# GPS_Altimetro_BoosterPack.net
KiCad netlist of a schematic drawn in Altium Designer
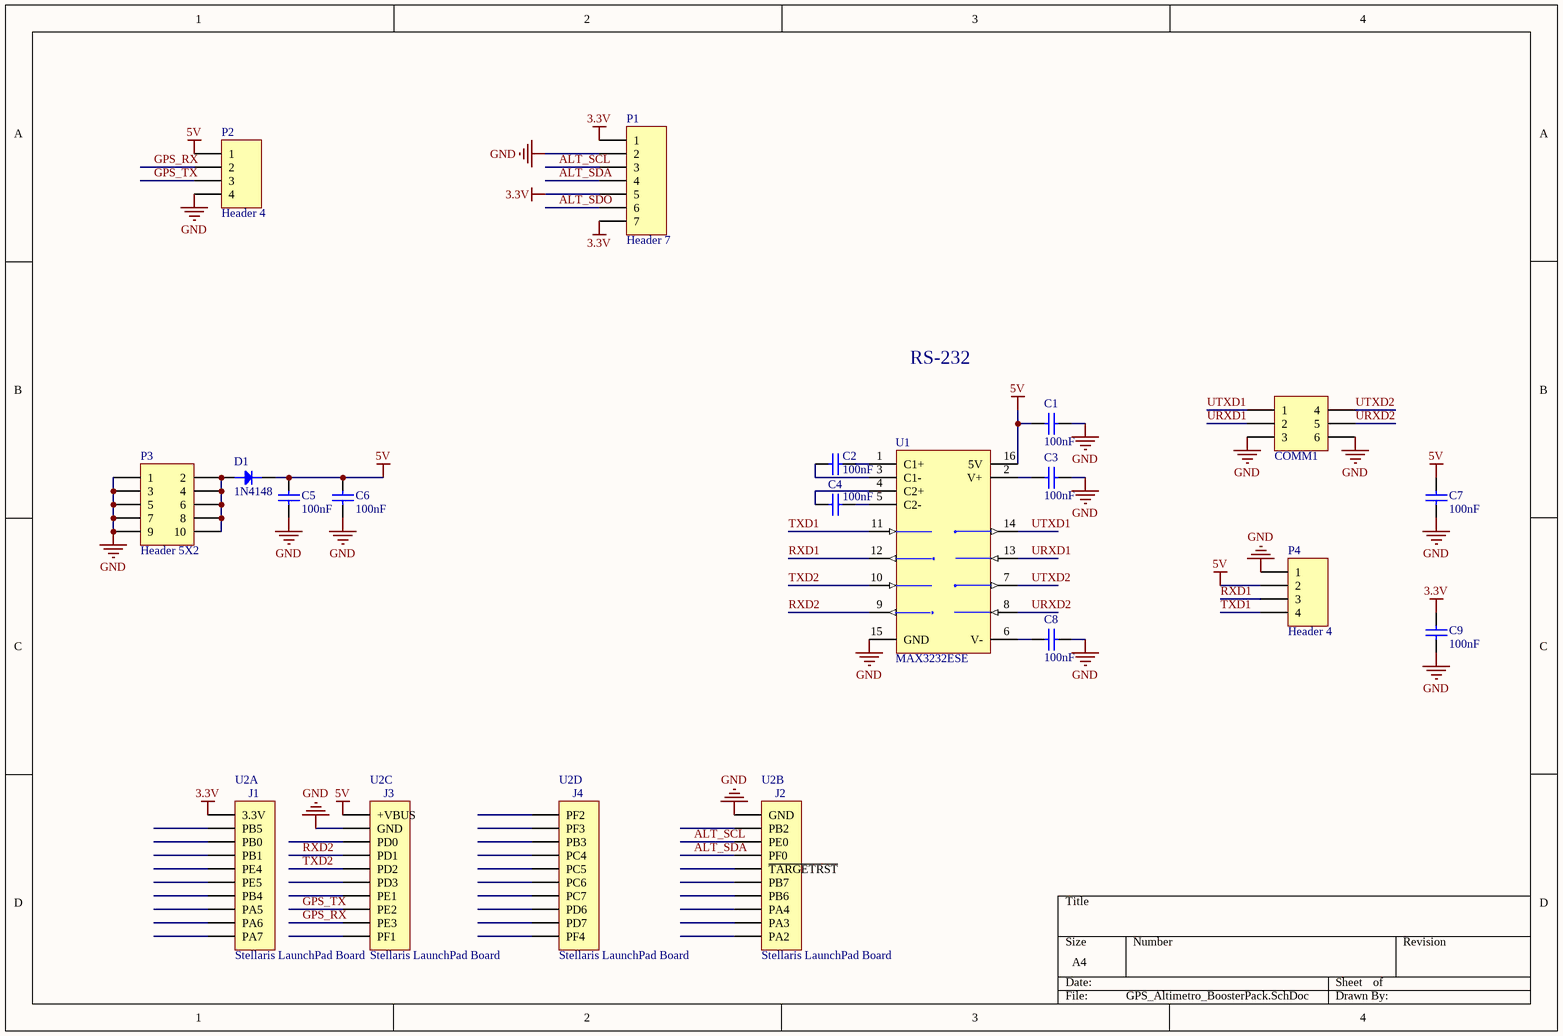
[diagram p0: GPS_Altimetro_BoosterPack.SchDoc]

(export (version "E")
  (design (tool "Eeschema 10.0.6"))
  (components
    (comp (ref "C1")
      (value "100nF")
      (footprint "0805_CAP")
      (fields (field (name "Comment") "Capacitor"))
      (libsource (lib "epf") (part "Cap"))
    )
    (comp (ref "C2")
      (value "100nF")
      (footprint "0805_CAP")
      (fields (field (name "Comment") "Capacitor"))
      (libsource (lib "epf") (part "Cap"))
    )
    (comp (ref "C3")
      (value "100nF")
      (footprint "0805_CAP")
      (fields (field (name "Comment") "Capacitor"))
      (libsource (lib "epf") (part "Cap"))
    )
    (comp (ref "C4")
      (value "100nF")
      (footprint "0805_CAP")
      (fields (field (name "Comment") "Capacitor"))
      (libsource (lib "epf") (part "Cap"))
    )
    (comp (ref "C5")
      (value "100nF")
      (footprint "0805_CAP")
      (fields (field (name "Comment") "Capacitor"))
      (libsource (lib "epf") (part "Cap"))
    )
    (comp (ref "C6")
      (value "100nF")
      (footprint "0805_CAP")
      (fields (field (name "Comment") "Capacitor"))
      (libsource (lib "epf") (part "Cap"))
    )
    (comp (ref "C7")
      (value "100nF")
      (footprint "0805_CAP")
      (fields (field (name "Comment") "Capacitor"))
      (libsource (lib "epf") (part "Cap"))
    )
    (comp (ref "C8")
      (value "100nF")
      (footprint "0805_CAP")
      (fields (field (name "Comment") "Capacitor"))
      (libsource (lib "epf") (part "Cap"))
    )
    (comp (ref "C9")
      (value "100nF")
      (footprint "0805_CAP")
      (fields (field (name "Comment") "Capacitor"))
      (libsource (lib "epf") (part "Cap"))
    )
    (comp (ref "COMM1")
      (value "AP_COMM")
      (footprint "HDR2X3_CEN")
      (description "Header, 3-Pin, Dual row")
      (fields (field (name "PUBLISHER") "Altium Limited"))
      (libsource (lib "epf") (part "AP_COMM"))
    )
    (comp (ref "D1") (value "1N4148") (footprint "1N4148SMD") (libsource (lib "epf") (part "1N4148")))
    (comp (ref "P1")
      (value "Header 7")
      (footprint "HDR1X7")
      (description "Header, 7-Pin")
      (fields (field (name "PUBLISHER") "Altium Limited"))
      (libsource (lib "Miscellaneous Connectors") (part "Header 7"))
    )
    (comp (ref "P2")
      (value "Header 4")
      (footprint "HDR1X4")
      (description "Header, 4-Pin")
      (fields (field (name "PUBLISHER") "Altium Limited"))
      (libsource (lib "Miscellaneous Connectors") (part "Header 4"))
    )
    (comp (ref "P3")
      (value "Header 5X2")
      (footprint "HDR2X5")
      (description "Header, 5-Pin, Dual row")
      (fields (field (name "PUBLISHER") "Altium Limited"))
      (libsource (lib "Miscellaneous Connectors") (part "Header 5X2"))
    )
    (comp (ref "P4")
      (value "Header 4")
      (footprint "HDR1X4")
      (description "Header, 4-Pin")
      (fields (field (name "PUBLISHER") "Altium Limited"))
      (libsource (lib "Miscellaneous Connectors") (part "Header 4"))
    )
    (comp (ref "U1")
      (value "MAX3232ESE")
      (footprint "SOIC127P602-16BN")
      (libsource (lib "epf") (part "MAX3232ESE+"))
    )
    (comp (ref "U2")
      (value "Stellaris LaunchPad Board")
      (footprint "LaunchPad")
      (description "Stellaris LaunchPad board")
      (fields (field (name "PUBLISHER") "Altium Limited"))
      (libsource (lib "epf") (part "Stellaris LaunchPad Board"))
    )
  )
  (nets
    (net (code "1") (name "/ALT_SCL") (class "Default")
      (node (ref "P1") (pin "3") (pinfunction "3_3") (pintype "passive"))
      (node (ref "U2") (pin "13") (pinfunction "PE0_13") (pintype "passive"))
    )
    (net (code "2") (name "/ALT_SDA") (class "Default")
      (node (ref "P1") (pin "4") (pinfunction "4_4") (pintype "passive"))
      (node (ref "U2") (pin "14") (pinfunction "PF0_14") (pintype "passive"))
    )
    (net (code "3") (name "/ALT_SDO") (class "Default")
      (node (ref "P1") (pin "6") (pinfunction "6_6") (pintype "passive"))
    )
    (net (code "4") (name "/GPS_RX") (class "Default")
      (node (ref "P2") (pin "2") (pinfunction "2_2") (pintype "passive"))
      (node (ref "U2") (pin "29") (pinfunction "PE3_29") (pintype "passive"))
    )
    (net (code "5") (name "/GPS_TX") (class "Default")
      (node (ref "P2") (pin "3") (pinfunction "3_3") (pintype "passive"))
      (node (ref "U2") (pin "28") (pinfunction "PE2_28") (pintype "passive"))
    )
    (net (code "6") (name "/RXD1") (class "Default")
      (node (ref "P4") (pin "3") (pinfunction "3_3") (pintype "passive"))
      (node (ref "U1") (pin "12") (pinfunction "R1OUT_12") (pintype "output"))
    )
    (net (code "7") (name "/RXD2") (class "Default")
      (node (ref "U1") (pin "9") (pinfunction "R2OUT_9") (pintype "output"))
      (node (ref "U2") (pin "24") (pinfunction "PD1_24") (pintype "passive"))
    )
    (net (code "8") (name "/TXD1") (class "Default")
      (node (ref "P4") (pin "4") (pinfunction "4_4") (pintype "passive"))
      (node (ref "U1") (pin "11") (pinfunction "T1IN_11") (pintype "input"))
    )
    (net (code "9") (name "/TXD2") (class "Default")
      (node (ref "U1") (pin "10") (pinfunction "T2IN_10") (pintype "input"))
      (node (ref "U2") (pin "25") (pinfunction "PD2_25") (pintype "passive"))
    )
    (net (code "10") (name "/URXD1") (class "Default")
      (node (ref "COMM1") (pin "2") (pinfunction "2_2") (pintype "passive"))
      (node (ref "U1") (pin "13") (pinfunction "R1IN_13") (pintype "input"))
    )
    (net (code "11") (name "/URXD2") (class "Default")
      (node (ref "COMM1") (pin "5") (pinfunction "5_5") (pintype "passive"))
      (node (ref "U1") (pin "8") (pinfunction "R2IN_8") (pintype "input"))
    )
    (net (code "12") (name "/UTXD1") (class "Default")
      (node (ref "COMM1") (pin "1") (pinfunction "1_1") (pintype "passive"))
      (node (ref "U1") (pin "14") (pinfunction "T1OUT_14") (pintype "output"))
    )
    (net (code "13") (name "/UTXD2") (class "Default")
      (node (ref "COMM1") (pin "4") (pinfunction "4_4") (pintype "passive"))
      (node (ref "U1") (pin "7") (pinfunction "T2OUT_7") (pintype "output"))
    )
    (net (code "14") (name "3.3V") (class "Default")
      (node (ref "C9") (pin "1") (pinfunction "1_1") (pintype "passive"))
      (node (ref "P1") (pin "1") (pinfunction "1_1") (pintype "passive"))
      (node (ref "P1") (pin "5") (pinfunction "5_5") (pintype "passive"))
      (node (ref "P1") (pin "7") (pinfunction "7_7") (pintype "passive"))
      (node (ref "U2") (pin "1") (pinfunction "3.3V_1") (pintype "passive"))
    )
    (net (code "15") (name "5V") (class "Default")
      (node (ref "C1") (pin "2") (pinfunction "2_2") (pintype "passive"))
      (node (ref "C5") (pin "1") (pinfunction "1_1") (pintype "passive"))
      (node (ref "C6") (pin "1") (pinfunction "1_1") (pintype "passive"))
      (node (ref "C7") (pin "1") (pinfunction "1_1") (pintype "passive"))
      (node (ref "D1") (pin "2") (pinfunction "K_2") (pintype "passive"))
      (node (ref "P2") (pin "1") (pinfunction "1_1") (pintype "passive"))
      (node (ref "P4") (pin "2") (pinfunction "2_2") (pintype "passive"))
      (node (ref "U1") (pin "16") (pinfunction "5V_16") (pintype "power_in"))
      (node (ref "U2") (pin "21") (pinfunction "+VBUS_21") (pintype "passive"))
    )
    (net (code "16") (name "GND") (class "Default")
      (node (ref "C1") (pin "1") (pinfunction "1_1") (pintype "passive"))
      (node (ref "C3") (pin "1") (pinfunction "1_1") (pintype "passive"))
      (node (ref "C5") (pin "2") (pinfunction "2_2") (pintype "passive"))
      (node (ref "C6") (pin "2") (pinfunction "2_2") (pintype "passive"))
      (node (ref "C7") (pin "2") (pinfunction "2_2") (pintype "passive"))
      (node (ref "C8") (pin "1") (pinfunction "1_1") (pintype "passive"))
      (node (ref "C9") (pin "2") (pinfunction "2_2") (pintype "passive"))
      (node (ref "COMM1") (pin "3") (pinfunction "3_3") (pintype "passive"))
      (node (ref "COMM1") (pin "6") (pinfunction "6_6") (pintype "passive"))
      (node (ref "P1") (pin "2") (pinfunction "2_2") (pintype "passive"))
      (node (ref "P2") (pin "4") (pinfunction "4_4") (pintype "passive"))
      (node (ref "P3") (pin "1") (pinfunction "1_1") (pintype "passive"))
      (node (ref "P3") (pin "3") (pinfunction "3_3") (pintype "passive"))
      (node (ref "P3") (pin "5") (pinfunction "5_5") (pintype "passive"))
      (node (ref "P3") (pin "7") (pinfunction "7_7") (pintype "passive"))
      (node (ref "P3") (pin "9") (pinfunction "9_9") (pintype "passive"))
      (node (ref "P4") (pin "1") (pinfunction "1_1") (pintype "passive"))
      (node (ref "U1") (pin "15") (pinfunction "GND_15") (pintype "power_in"))
      (node (ref "U2") (pin "11") (pinfunction "GND_11") (pintype "passive"))
      (node (ref "U2") (pin "22") (pinfunction "GND_22") (pintype "passive"))
    )
    (net (code "17") (name "Net-(D1-A)") (class "Default")
      (node (ref "D1") (pin "1") (pinfunction "A_1") (pintype "passive"))
      (node (ref "P3") (pin "10") (pinfunction "10_10") (pintype "passive"))
      (node (ref "P3") (pin "2") (pinfunction "2_2") (pintype "passive"))
      (node (ref "P3") (pin "4") (pinfunction "4_4") (pintype "passive"))
      (node (ref "P3") (pin "6") (pinfunction "6_6") (pintype "passive"))
      (node (ref "P3") (pin "8") (pinfunction "8_8") (pintype "passive"))
    )
    (net (code "18") (name "Net-(U1-C1+)") (class "Default")
      (node (ref "C2") (pin "1") (pinfunction "1_1") (pintype "passive"))
      (node (ref "U1") (pin "1") (pinfunction "C1+_1") (pintype "passive"))
    )
    (net (code "19") (name "Net-(U1-C1-)") (class "Default")
      (node (ref "C2") (pin "2") (pinfunction "2_2") (pintype "passive"))
      (node (ref "U1") (pin "3") (pinfunction "C1-_3") (pintype "passive"))
    )
    (net (code "20") (name "Net-(U1-C2+)") (class "Default")
      (node (ref "C4") (pin "2") (pinfunction "2_2") (pintype "passive"))
      (node (ref "U1") (pin "4") (pinfunction "C2+_4") (pintype "passive"))
    )
    (net (code "21") (name "Net-(U1-C2-)") (class "Default")
      (node (ref "C4") (pin "1") (pinfunction "1_1") (pintype "passive"))
      (node (ref "U1") (pin "5") (pinfunction "C2-_5") (pintype "passive"))
    )
    (net (code "22") (name "Net-(U1-V+)") (class "Default")
      (node (ref "C3") (pin "2") (pinfunction "2_2") (pintype "passive"))
      (node (ref "U1") (pin "2") (pinfunction "V+_2") (pintype "power_in"))
    )
    (net (code "23") (name "Net-(U1-V-)") (class "Default")
      (node (ref "C8") (pin "2") (pinfunction "2_2") (pintype "passive"))
      (node (ref "U1") (pin "6") (pinfunction "V-_6") (pintype "power_in"))
    )
    (net (code "24") (name "unconnected-(U2A-PA5-Pad8)") (class "Default")
      (node (ref "U2") (pin "8") (pinfunction "PA5_8") (pintype "passive"))
    )
    (net (code "25") (name "unconnected-(U2A-PA6-Pad9)") (class "Default")
      (node (ref "U2") (pin "9") (pinfunction "PA6_9") (pintype "passive"))
    )
    (net (code "26") (name "unconnected-(U2A-PA7-Pad10)") (class "Default")
      (node (ref "U2") (pin "10") (pinfunction "PA7_10") (pintype "passive"))
    )
    (net (code "27") (name "unconnected-(U2A-PB0-Pad3)") (class "Default")
      (node (ref "U2") (pin "3") (pinfunction "PB0_3") (pintype "passive"))
    )
    (net (code "28") (name "unconnected-(U2A-PB1-Pad4)") (class "Default")
      (node (ref "U2") (pin "4") (pinfunction "PB1_4") (pintype "passive"))
    )
    (net (code "29") (name "unconnected-(U2A-PB4-Pad7)") (class "Default")
      (node (ref "U2") (pin "7") (pinfunction "PB4_7") (pintype "passive"))
    )
    (net (code "30") (name "unconnected-(U2A-PB5-Pad2)") (class "Default")
      (node (ref "U2") (pin "2") (pinfunction "PB5_2") (pintype "passive"))
    )
    (net (code "31") (name "unconnected-(U2A-PE4-Pad5)") (class "Default")
      (node (ref "U2") (pin "5") (pinfunction "PE4_5") (pintype "passive"))
    )
    (net (code "32") (name "unconnected-(U2A-PE5-Pad6)") (class "Default")
      (node (ref "U2") (pin "6") (pinfunction "PE5_6") (pintype "passive"))
    )
    (net (code "33") (name "unconnected-(U2B-PA2-Pad20)") (class "Default")
      (node (ref "U2") (pin "20") (pinfunction "PA2_20") (pintype "passive"))
    )
    (net (code "34") (name "unconnected-(U2B-PA3-Pad19)") (class "Default")
      (node (ref "U2") (pin "19") (pinfunction "PA3_19") (pintype "passive"))
    )
    (net (code "35") (name "unconnected-(U2B-PA4-Pad18)") (class "Default")
      (node (ref "U2") (pin "18") (pinfunction "PA4_18") (pintype "passive"))
    )
    (net (code "36") (name "unconnected-(U2B-PB2-Pad12)") (class "Default")
      (node (ref "U2") (pin "12") (pinfunction "PB2_12") (pintype "passive"))
    )
    (net (code "37") (name "unconnected-(U2B-PB6-Pad17)") (class "Default")
      (node (ref "U2") (pin "17") (pinfunction "PB6_17") (pintype "passive"))
    )
    (net (code "38") (name "unconnected-(U2B-PB7-Pad16)") (class "Default")
      (node (ref "U2") (pin "16") (pinfunction "PB7_16") (pintype "passive"))
    )
    (net (code "39") (name "unconnected-(U2B-~{TARGETRST}-Pad15)") (class "Default")
      (node (ref "U2") (pin "15") (pinfunction "~{TARGETRST}_15") (pintype "passive"))
    )
    (net (code "40") (name "unconnected-(U2C-PD0-Pad23)") (class "Default")
      (node (ref "U2") (pin "23") (pinfunction "PD0_23") (pintype "passive"))
    )
    (net (code "41") (name "unconnected-(U2C-PD3-Pad26)") (class "Default")
      (node (ref "U2") (pin "26") (pinfunction "PD3_26") (pintype "passive"))
    )
    (net (code "42") (name "unconnected-(U2C-PE1-Pad27)") (class "Default")
      (node (ref "U2") (pin "27") (pinfunction "PE1_27") (pintype "passive"))
    )
    (net (code "43") (name "unconnected-(U2C-PF1-Pad30)") (class "Default")
      (node (ref "U2") (pin "30") (pinfunction "PF1_30") (pintype "passive"))
    )
    (net (code "44") (name "unconnected-(U2D-PB3-Pad33)") (class "Default")
      (node (ref "U2") (pin "33") (pinfunction "PB3_33") (pintype "passive"))
    )
    (net (code "45") (name "unconnected-(U2D-PC4-Pad34)") (class "Default")
      (node (ref "U2") (pin "34") (pinfunction "PC4_34") (pintype "passive"))
    )
    (net (code "46") (name "unconnected-(U2D-PC5-Pad35)") (class "Default")
      (node (ref "U2") (pin "35") (pinfunction "PC5_35") (pintype "passive"))
    )
    (net (code "47") (name "unconnected-(U2D-PC6-Pad36)") (class "Default")
      (node (ref "U2") (pin "36") (pinfunction "PC6_36") (pintype "passive"))
    )
    (net (code "48") (name "unconnected-(U2D-PC7-Pad37)") (class "Default")
      (node (ref "U2") (pin "37") (pinfunction "PC7_37") (pintype "passive"))
    )
    (net (code "49") (name "unconnected-(U2D-PD6-Pad38)") (class "Default")
      (node (ref "U2") (pin "38") (pinfunction "PD6_38") (pintype "passive"))
    )
    (net (code "50") (name "unconnected-(U2D-PD7-Pad39)") (class "Default")
      (node (ref "U2") (pin "39") (pinfunction "PD7_39") (pintype "passive"))
    )
    (net (code "51") (name "unconnected-(U2D-PF2-Pad31)") (class "Default")
      (node (ref "U2") (pin "31") (pinfunction "PF2_31") (pintype "passive"))
    )
    (net (code "52") (name "unconnected-(U2D-PF3-Pad32)") (class "Default")
      (node (ref "U2") (pin "32") (pinfunction "PF3_32") (pintype "passive"))
    )
    (net (code "53") (name "unconnected-(U2D-PF4-Pad40)") (class "Default")
      (node (ref "U2") (pin "40") (pinfunction "PF4_40") (pintype "passive"))
    )
  )
)
